# MOD-v2-3_MOD-Strips.net
KiCad netlist of a schematic drawn in EAGLE
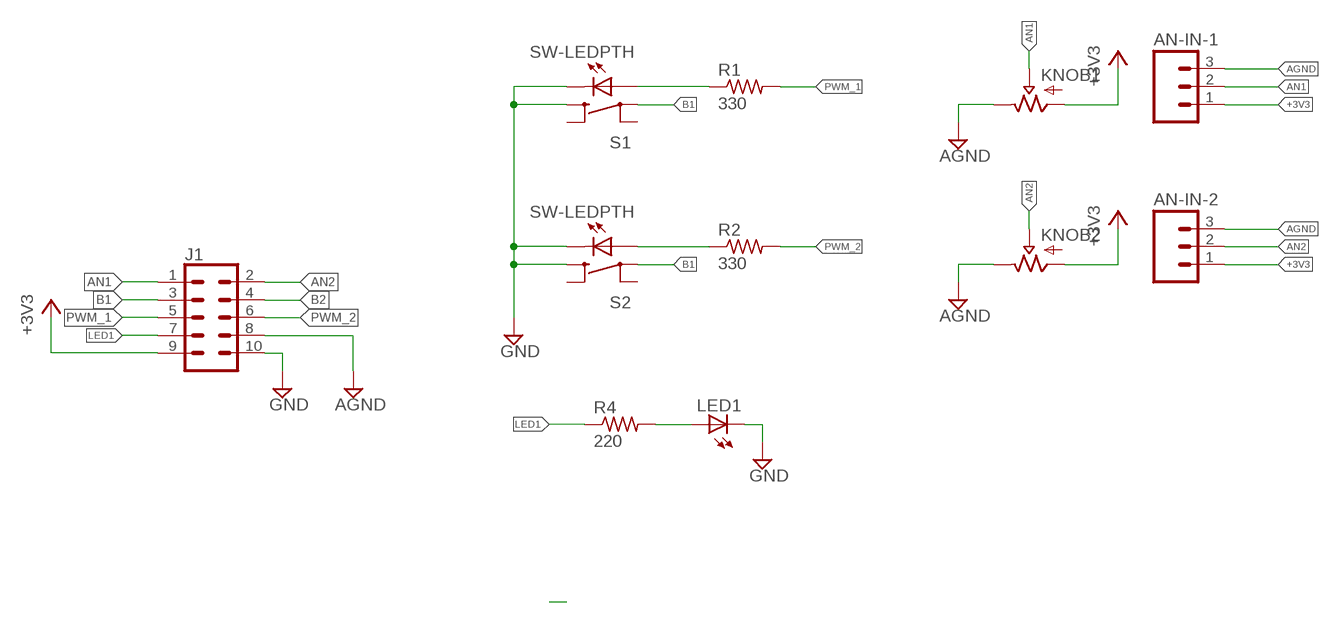
[diagram p0: schematic, sheet 1]

(export (version "E")
  (design (tool "Eeschema 10.0.6"))
  (components
    (comp (ref "AN-IN-1")
      (value "M031X03_NO_SILK")
      (footprint "eagle-import:1X03_NO_SILK")
      (libsource (lib "eagle-import") (part "M031X03_NO_SILK"))
    )
    (comp (ref "AN-IN-2")
      (value "M031X03_NO_SILK")
      (footprint "eagle-import:1X03_NO_SILK")
      (libsource (lib "eagle-import") (part "M031X03_NO_SILK"))
    )
    (comp (ref "J1")
      (value "CONN_05X2SHD_LOCK")
      (footprint "eagle-import:2X5-SHROUDED_LOCK")
      (libsource (lib "eagle-import") (part "CONN_05X2SHD_LOCK"))
    )
    (comp (ref "KNOB1")
      (value "POTALPHA_RD901")
      (footprint "eagle-import:POT_ALPHA_RD901F-40-(L)R1")
      (libsource (lib "eagle-import") (part "POTALPHA_RD901"))
    )
    (comp (ref "KNOB2")
      (value "POTALPHA_RD901")
      (footprint "eagle-import:POT_ALPHA_RD901F-40-(L)R1")
      (libsource (lib "eagle-import") (part "POTALPHA_RD901"))
    )
    (comp (ref "LED1")
      (value "LED3MM")
      (footprint "eagle-import:LED3MM")
      (libsource (lib "eagle-import") (part "LED3MM"))
    )
    (comp (ref "R1")
      (value "330")
      (footprint "eagle-import:0204_5")
      (libsource (lib "eagle-import") (part "R-US_0204/5"))
    )
    (comp (ref "R2")
      (value "330")
      (footprint "eagle-import:0204_5")
      (libsource (lib "eagle-import") (part "R-US_0204/5"))
    )
    (comp (ref "R4")
      (value "220")
      (footprint "eagle-import:0204_7")
      (libsource (lib "eagle-import") (part "R-US_0204/7"))
    )
    (comp (ref "S1")
      (value "SW-LEDPTH")
      (footprint "eagle-import:TR2-SWITCH-MOMENTARY-LED")
      (libsource (lib "eagle-import") (part "SW-LEDPTH"))
    )
    (comp (ref "S2")
      (value "SW-LEDPTH")
      (footprint "eagle-import:TR2-SWITCH-MOMENTARY-LED")
      (libsource (lib "eagle-import") (part "SW-LEDPTH"))
    )
  )
  (nets
    (net (code "1") (name "+3V3") (class "Default")
      (node (ref "AN-IN-1") (pin "1") (pinfunction "1_1") (pintype "passive"))
      (node (ref "AN-IN-2") (pin "1") (pinfunction "1_1") (pintype "passive"))
      (node (ref "J1") (pin "9") (pinfunction "9_9") (pintype "passive"))
      (node (ref "KNOB1") (pin "1") (pinfunction "IN_1") (pintype "passive"))
      (node (ref "KNOB2") (pin "1") (pinfunction "IN_1") (pintype "passive"))
    )
    (net (code "2") (name "AGND") (class "Default")
      (node (ref "AN-IN-1") (pin "3") (pinfunction "3_3") (pintype "passive"))
      (node (ref "AN-IN-2") (pin "3") (pinfunction "3_3") (pintype "passive"))
      (node (ref "J1") (pin "8") (pinfunction "8_8") (pintype "passive"))
      (node (ref "KNOB1") (pin "3") (pinfunction "OUT_3") (pintype "passive"))
      (node (ref "KNOB2") (pin "3") (pinfunction "OUT_3") (pintype "passive"))
    )
    (net (code "3") (name "AN1") (class "Default")
      (node (ref "AN-IN-1") (pin "2") (pinfunction "2_2") (pintype "passive"))
      (node (ref "J1") (pin "1") (pinfunction "1_1") (pintype "passive"))
      (node (ref "KNOB1") (pin "2") (pinfunction "WIPER_2") (pintype "passive"))
    )
    (net (code "4") (name "AN2") (class "Default")
      (node (ref "AN-IN-2") (pin "2") (pinfunction "2_2") (pintype "passive"))
      (node (ref "J1") (pin "2") (pinfunction "2_2") (pintype "passive"))
      (node (ref "KNOB2") (pin "2") (pinfunction "WIPER_2") (pintype "passive"))
    )
    (net (code "5") (name "B1") (class "Default")
      (node (ref "J1") (pin "3") (pinfunction "3_3") (pintype "passive"))
      (node (ref "S1") (pin "3") (pinfunction "3_3") (pintype "passive"))
      (node (ref "S2") (pin "3") (pinfunction "3_3") (pintype "passive"))
    )
    (net (code "6") (name "B2") (class "Default")
      (node (ref "J1") (pin "4") (pinfunction "4_4") (pintype "passive"))
    )
    (net (code "7") (name "GND") (class "Default")
      (node (ref "J1") (pin "10") (pinfunction "10_10") (pintype "passive"))
      (node (ref "LED1") (pin "K") (pinfunction "C_K") (pintype "passive"))
      (node (ref "S1") (pin "1") (pinfunction "1_1") (pintype "passive"))
      (node (ref "S1") (pin "C") (pinfunction "C_C") (pintype "passive"))
      (node (ref "S2") (pin "1") (pinfunction "1_1") (pintype "passive"))
      (node (ref "S2") (pin "C") (pinfunction "C_C") (pintype "passive"))
    )
    (net (code "8") (name "LED1") (class "Default")
      (node (ref "J1") (pin "7") (pinfunction "7_7") (pintype "passive"))
      (node (ref "R4") (pin "1") (pinfunction "1_1") (pintype "passive"))
    )
    (net (code "9") (name "Net-(LED1-PadA)") (class "Default")
      (node (ref "LED1") (pin "A") (pinfunction "A_A") (pintype "passive"))
      (node (ref "R4") (pin "2") (pinfunction "2_2") (pintype "passive"))
    )
    (net (code "10") (name "Net-(R1-Pad1)") (class "Default")
      (node (ref "R1") (pin "1") (pinfunction "1_1") (pintype "passive"))
      (node (ref "S1") (pin "A") (pinfunction "A_A") (pintype "passive"))
    )
    (net (code "11") (name "Net-(R2-Pad1)") (class "Default")
      (node (ref "R2") (pin "1") (pinfunction "1_1") (pintype "passive"))
      (node (ref "S2") (pin "A") (pinfunction "A_A") (pintype "passive"))
    )
    (net (code "12") (name "PWM_1") (class "Default")
      (node (ref "J1") (pin "5") (pinfunction "5_5") (pintype "passive"))
      (node (ref "R1") (pin "2") (pinfunction "2_2") (pintype "passive"))
    )
    (net (code "13") (name "PWM_2") (class "Default")
      (node (ref "J1") (pin "6") (pinfunction "6_6") (pintype "passive"))
      (node (ref "R2") (pin "2") (pinfunction "2_2") (pintype "passive"))
    )
    (net (code "14") (name "unconnected-(S1-Pad2)") (class "Default")
      (node (ref "S1") (pin "2") (pinfunction "2_2") (pintype "passive"))
    )
    (net (code "15") (name "unconnected-(S1-Pad4)") (class "Default")
      (node (ref "S1") (pin "4") (pinfunction "4_4") (pintype "passive"))
    )
    (net (code "16") (name "unconnected-(S2-Pad2)") (class "Default")
      (node (ref "S2") (pin "2") (pinfunction "2_2") (pintype "passive"))
    )
    (net (code "17") (name "unconnected-(S2-Pad4)") (class "Default")
      (node (ref "S2") (pin "4") (pinfunction "4_4") (pintype "passive"))
    )
  )
)
